# LB_BIT_w6_ARDUINO-v03_4-5_OHW.net
KiCad netlist of a schematic drawn in EAGLE
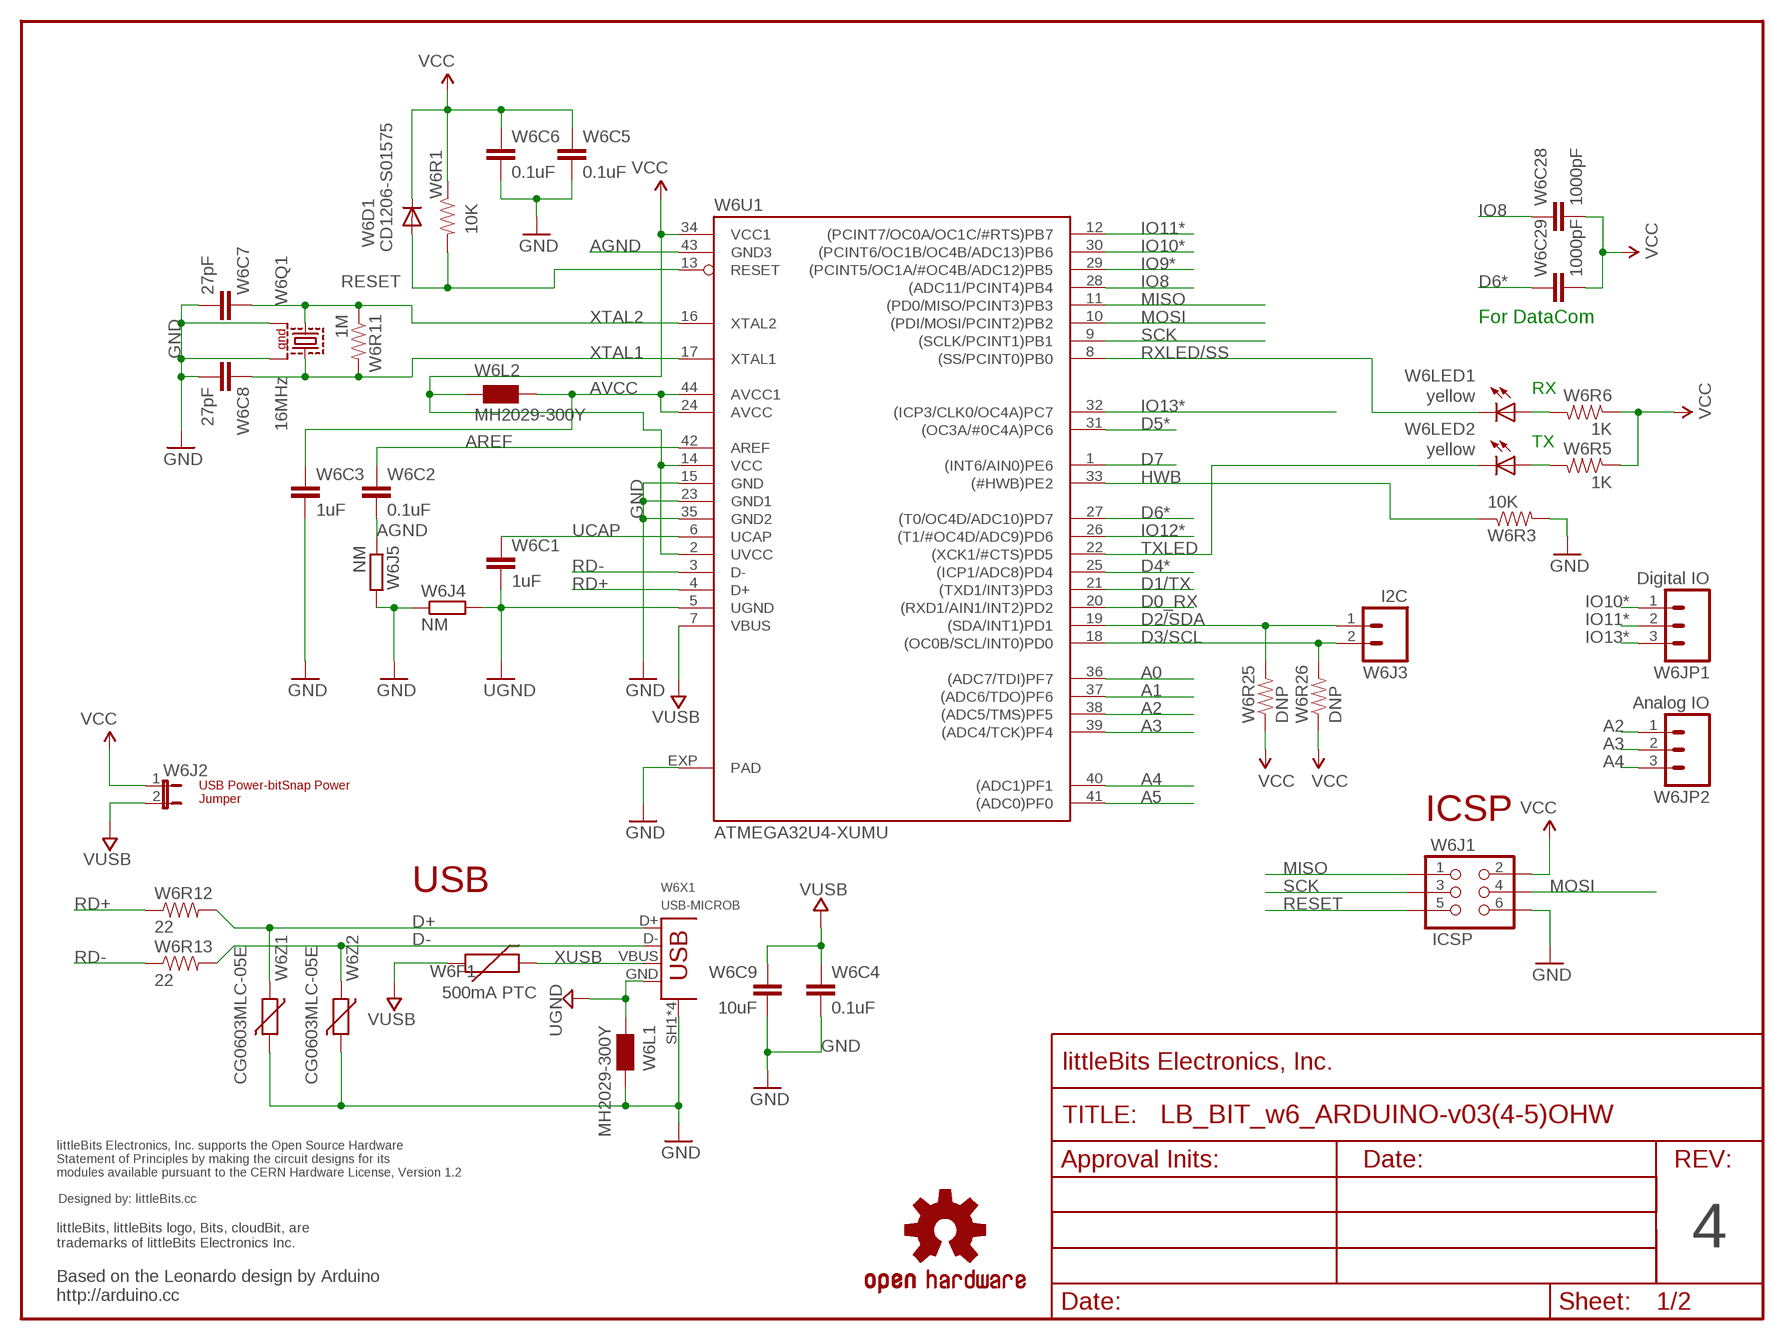
[diagram p0: schematic, sheet 1]
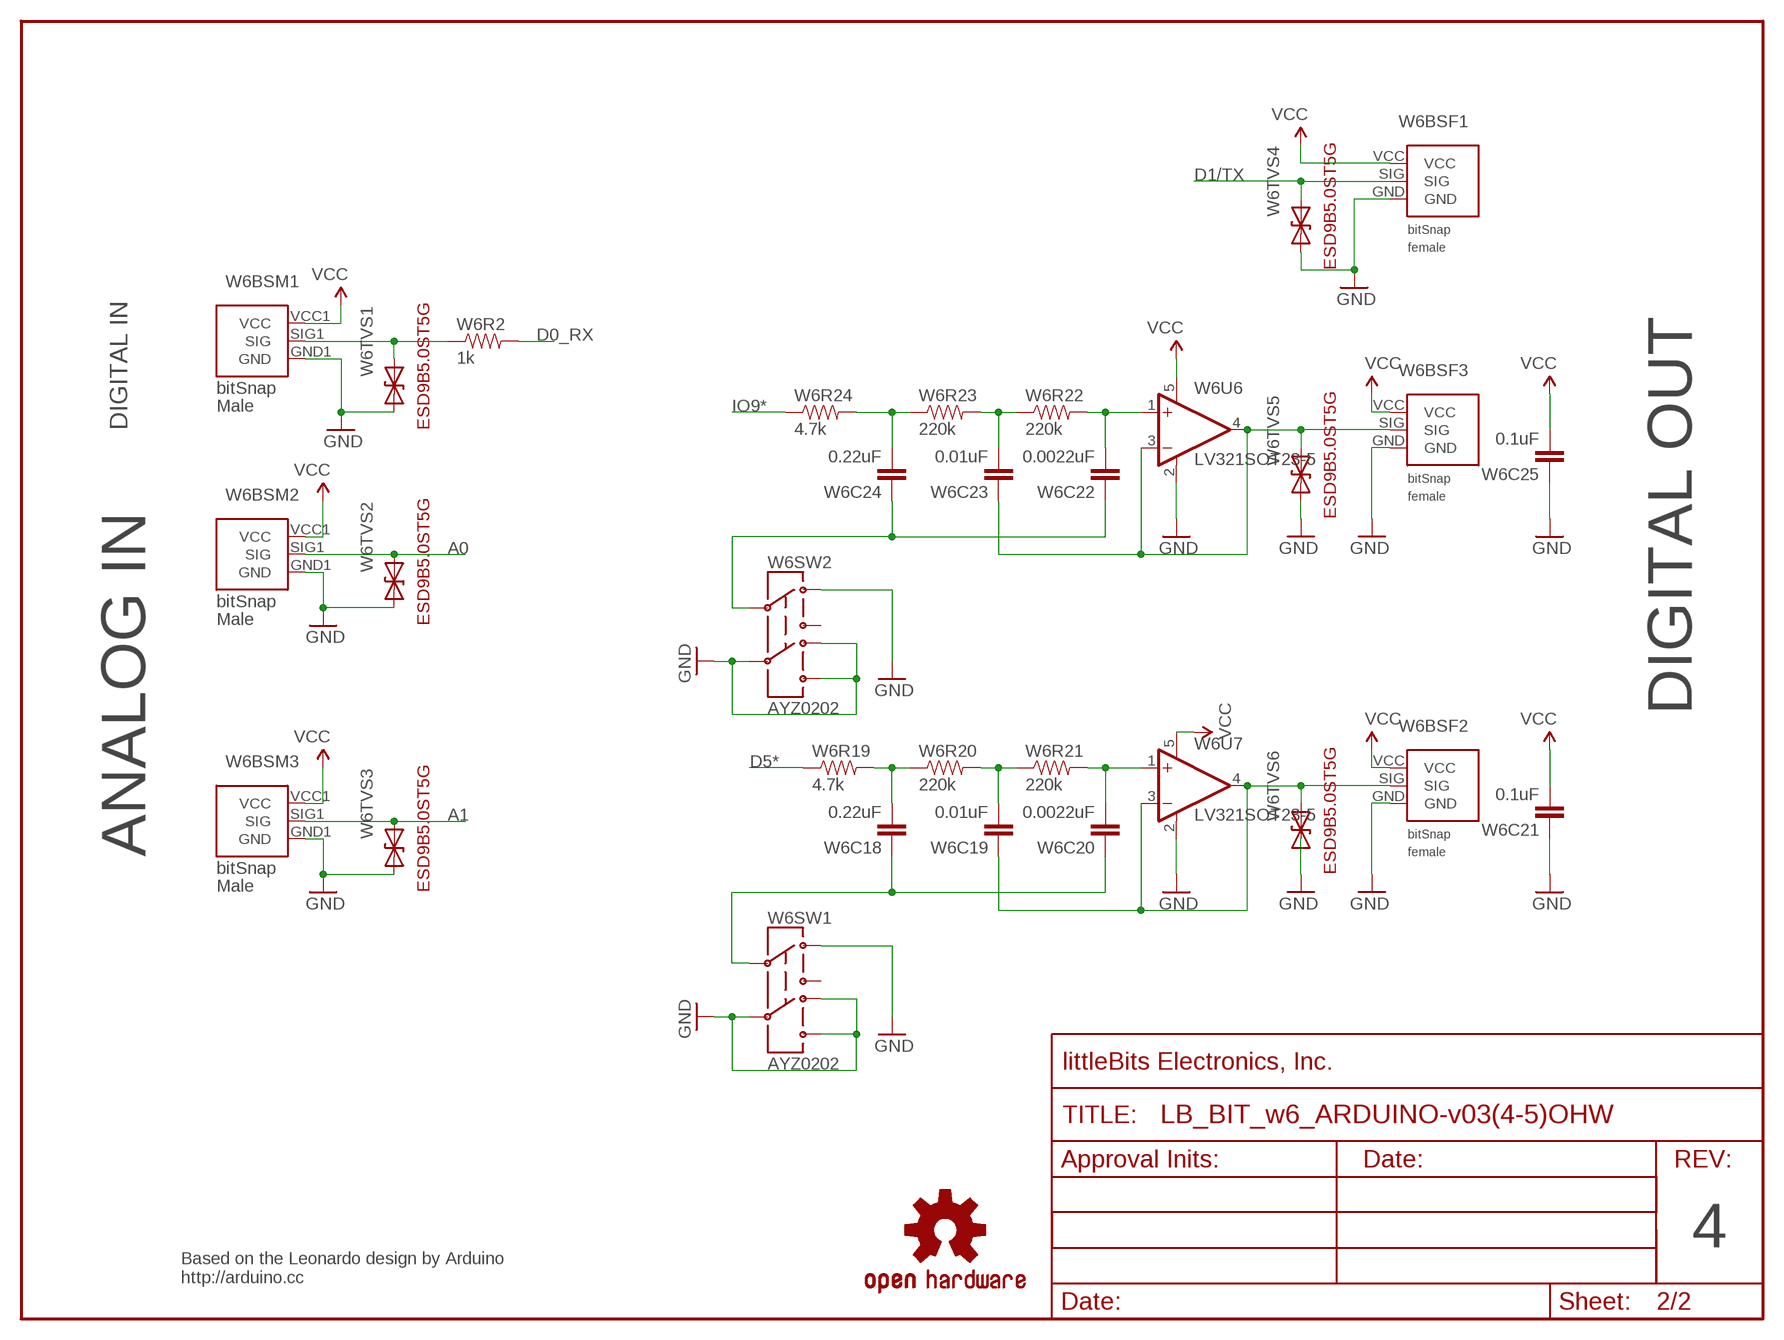
[diagram p1: schematic, sheet 2]

(export (version "E")
  (design (tool "Eeschema 10.0.6"))
  (components
    (comp (ref "FRAME2")
      (value "FRAME-LETTER-OHWOHW")
      (footprint "eagle-import:FABDWG01-OHW")
      (libsource (lib "eagle-import") (part "FRAME-LETTER-OHWOHW"))
    )
    (comp (ref "U$52")
      (value "OSHW-LOGOL")
      (footprint "eagle-import:OSHW-LOGO-L")
      (libsource (lib "eagle-import") (part "OSHW-LOGOL"))
    )
    (comp (ref "U$67")
      (value "OSHWCREDIT")
      (footprint "eagle-import:OSHWCREDIT")
      (libsource (lib "eagle-import") (part "OSHWCREDIT"))
    )
    (comp (ref "W6C1")
      (value "1uF")
      (footprint "eagle-import:CAP-0603")
      (libsource (lib "eagle-import") (part "CAPCAP-0603"))
    )
    (comp (ref "W6C2")
      (value "0.1uF")
      (footprint "eagle-import:CAP-0603")
      (libsource (lib "eagle-import") (part "CAPCAP-0603"))
    )
    (comp (ref "W6C3")
      (value "1uF")
      (footprint "eagle-import:CAP-0603")
      (libsource (lib "eagle-import") (part "CAPCAP-0603"))
    )
    (comp (ref "W6C4")
      (value "0.1uF")
      (footprint "eagle-import:CAP-0603")
      (libsource (lib "eagle-import") (part "CAPCAP-0603"))
    )
    (comp (ref "W6C5")
      (value "0.1uF")
      (footprint "eagle-import:CAP-0603")
      (libsource (lib "eagle-import") (part "CAPCAP-0603"))
    )
    (comp (ref "W6C6")
      (value "0.1uF")
      (footprint "eagle-import:CAP-0603")
      (libsource (lib "eagle-import") (part "CAPCAP-0603"))
    )
    (comp (ref "W6C7")
      (value "27pF")
      (footprint "eagle-import:CAP-0603")
      (libsource (lib "eagle-import") (part "CAPCAP-0603"))
    )
    (comp (ref "W6C8")
      (value "27pF")
      (footprint "eagle-import:CAP-0603")
      (libsource (lib "eagle-import") (part "CAPCAP-0603"))
    )
    (comp (ref "W6C9")
      (value "10uF")
      (footprint "eagle-import:CAP-0805")
      (libsource (lib "eagle-import") (part "CAPCAP-0805"))
    )
    (comp (ref "W6C28")
      (value "1000pF")
      (footprint "eagle-import:CAP-0603")
      (libsource (lib "eagle-import") (part "CAPCAP-0603"))
    )
    (comp (ref "W6C29")
      (value "1000pF")
      (footprint "eagle-import:CAP-0603")
      (libsource (lib "eagle-import") (part "CAPCAP-0603"))
    )
    (comp (ref "W6D1")
      (value "CD1206-S01575")
      (footprint "eagle-import:MINIMELF")
      (libsource (lib "eagle-import") (part "DIODE-MINIMELF"))
    )
    (comp (ref "W6F1")
      (value "500mA PTC")
      (footprint "eagle-import:PTC-1206")
      (libsource (lib "eagle-import") (part "PTC"))
    )
    (comp (ref "W6J1")
      (value "ICSP")
      (footprint "eagle-import:2X03")
      (libsource (lib "eagle-import") (part "HDR-2X3"))
    )
    (comp (ref "W6J2")
      (value "JUMPER-2SMD-NO")
      (footprint "eagle-import:SJ_2S-NO")
      (libsource (lib "eagle-import") (part "JUMPER-2SMD-NO"))
    )
    (comp (ref "W6J3")
      (value "I2C")
      (footprint "eagle-import:SIP2-SM-0.1IN")
      (libsource (lib "eagle-import") (part "HDR-20.1IN_NOS.S."))
    )
    (comp (ref "W6J4")
      (value "NM")
      (footprint "eagle-import:R0402")
      (libsource (lib "eagle-import") (part "R-EU_R0402"))
    )
    (comp (ref "W6J5")
      (value "NM")
      (footprint "eagle-import:R0402")
      (libsource (lib "eagle-import") (part "R-EU_R0402"))
    )
    (comp (ref "W6JP1")
      (value "Digital IO")
      (footprint "eagle-import:1X03")
      (libsource (lib "eagle-import") (part "M03PTH"))
    )
    (comp (ref "W6JP2")
      (value "Analog IO")
      (footprint "eagle-import:1X03")
      (libsource (lib "eagle-import") (part "M03PTH"))
    )
    (comp (ref "W6L1")
      (value "MH2029-300Y")
      (footprint "eagle-import:0805")
      (libsource (lib "eagle-import") (part "WE-CBF_0805"))
    )
    (comp (ref "W6L2")
      (value "MH2029-300Y")
      (footprint "eagle-import:0805")
      (libsource (lib "eagle-import") (part "WE-CBF_0805"))
    )
    (comp (ref "W6LED1")
      (value "yellow")
      (footprint "eagle-import:LED-1206")
      (libsource (lib "eagle-import") (part "LED1206"))
    )
    (comp (ref "W6LED2")
      (value "yellow")
      (footprint "eagle-import:LED-1206")
      (libsource (lib "eagle-import") (part "LED1206"))
    )
    (comp (ref "W6Q1")
      (value "16MHz")
      (footprint "eagle-import:CRYSTAL-SMD-7B-SERIES-5X3.2MM")
      (fields (field (name "MFG") "TXC") (field (name "MPN") "7B SERIES"))
      (libsource (lib "eagle-import") (part "CRYSTAL-SMD-7B-SERIES-TXC"))
    )
    (comp (ref "W6R1")
      (value "10K")
      (footprint "eagle-import:RES-0603")
      (libsource (lib "eagle-import") (part "RESISTOR0603"))
    )
    (comp (ref "W6R3")
      (value "10K")
      (footprint "eagle-import:RES-0603")
      (libsource (lib "eagle-import") (part "RESISTOR0603"))
    )
    (comp (ref "W6R5")
      (value "1K")
      (footprint "eagle-import:RES-0603")
      (libsource (lib "eagle-import") (part "RESISTOR0603"))
    )
    (comp (ref "W6R6")
      (value "1K")
      (footprint "eagle-import:RES-0603")
      (libsource (lib "eagle-import") (part "RESISTOR0603"))
    )
    (comp (ref "W6R11")
      (value "1M")
      (footprint "eagle-import:RES-0603")
      (libsource (lib "eagle-import") (part "RESISTOR0603"))
    )
    (comp (ref "W6R12")
      (value "22")
      (footprint "eagle-import:RES-0603")
      (libsource (lib "eagle-import") (part "RESISTOR0603"))
    )
    (comp (ref "W6R13")
      (value "22")
      (footprint "eagle-import:RES-0603")
      (libsource (lib "eagle-import") (part "RESISTOR0603"))
    )
    (comp (ref "W6R25")
      (value "DNP")
      (footprint "eagle-import:RES-0603")
      (libsource (lib "eagle-import") (part "RESISTOR0603"))
    )
    (comp (ref "W6R26")
      (value "DNP")
      (footprint "eagle-import:RES-0603")
      (libsource (lib "eagle-import") (part "RESISTOR0603"))
    )
    (comp (ref "W6U1")
      (value "ATMEGA32U4-XUMU")
      (footprint "eagle-import:QFN44ML7X7")
      (libsource (lib "eagle-import") (part "ATMEGA32U4-XUMU"))
    )
    (comp (ref "W6X1")
      (value "USB-MICROB")
      (footprint "eagle-import:USB-MICROB-AUK-DRILLS")
      (fields (field (name "MFG") "AUK") (field (name "MPN") "MCSB5ABSW-4-GXX-R1K-H"))
      (libsource (lib "eagle-import") (part "USB-MICROB-DRILLS"))
    )
    (comp (ref "W6Z1")
      (value "CG0603MLC-05E")
      (footprint "eagle-import:CT_CN0603")
      (libsource (lib "eagle-import") (part "VARISTORCN0603"))
    )
    (comp (ref "W6Z2")
      (value "CG0603MLC-05E")
      (footprint "eagle-import:CT_CN0603")
      (libsource (lib "eagle-import") (part "VARISTORCN0603"))
    )
    (comp (ref "U$54")
      (value "FRAME-LETTER-OHWOHW")
      (footprint "eagle-import:FABDWG01-OHW")
      (libsource (lib "eagle-import") (part "FRAME-LETTER-OHWOHW"))
    )
    (comp (ref "U$70")
      (value "OSHW-LOGOL")
      (footprint "eagle-import:OSHW-LOGO-L")
      (libsource (lib "eagle-import") (part "OSHW-LOGOL"))
    )
    (comp (ref "W6BSF1")
      (value "BITSNAP_V03_FEMALE")
      (footprint "eagle-import:BITSNAP_V03_FEMALE")
      (libsource (lib "eagle-import") (part "BITSNAP_V03_FEMALE"))
    )
    (comp (ref "W6BSF2")
      (value "BITSNAP_V03_FEMALE")
      (footprint "eagle-import:BITSNAP_V03_FEMALE")
      (libsource (lib "eagle-import") (part "BITSNAP_V03_FEMALE"))
    )
    (comp (ref "W6BSF3")
      (value "BITSNAP_V03_FEMALE")
      (footprint "eagle-import:BITSNAP_V03_FEMALE")
      (libsource (lib "eagle-import") (part "BITSNAP_V03_FEMALE"))
    )
    (comp (ref "W6BSM1")
      (value "BITSNAP_V03_MALE")
      (footprint "eagle-import:BITSNAP_V03_MALE")
      (libsource (lib "eagle-import") (part "BITSNAP_V03_MALE"))
    )
    (comp (ref "W6BSM2")
      (value "BITSNAP_V03_MALE")
      (footprint "eagle-import:BITSNAP_V03_MALE")
      (libsource (lib "eagle-import") (part "BITSNAP_V03_MALE"))
    )
    (comp (ref "W6BSM3")
      (value "BITSNAP_V03_MALE")
      (footprint "eagle-import:BITSNAP_V03_MALE")
      (libsource (lib "eagle-import") (part "BITSNAP_V03_MALE"))
    )
    (comp (ref "W6C18")
      (value "0.22uF")
      (footprint "eagle-import:CAP-0603")
      (libsource (lib "eagle-import") (part "CAPCAP-0603"))
    )
    (comp (ref "W6C19")
      (value "0.01uF")
      (footprint "eagle-import:CAP-0603")
      (libsource (lib "eagle-import") (part "CAPCAP-0603"))
    )
    (comp (ref "W6C20")
      (value "0.0022uF")
      (footprint "eagle-import:CAP-0603")
      (libsource (lib "eagle-import") (part "CAPCAP-0603"))
    )
    (comp (ref "W6C21")
      (value "0.1uF")
      (footprint "eagle-import:CAP-0603")
      (libsource (lib "eagle-import") (part "CAPCAP-0603"))
    )
    (comp (ref "W6C22")
      (value "0.0022uF")
      (footprint "eagle-import:CAP-0603")
      (libsource (lib "eagle-import") (part "CAPCAP-0603"))
    )
    (comp (ref "W6C23")
      (value "0.01uF")
      (footprint "eagle-import:CAP-0603")
      (libsource (lib "eagle-import") (part "CAPCAP-0603"))
    )
    (comp (ref "W6C24")
      (value "0.22uF")
      (footprint "eagle-import:CAP-0603")
      (libsource (lib "eagle-import") (part "CAPCAP-0603"))
    )
    (comp (ref "W6C25")
      (value "0.1uF")
      (footprint "eagle-import:CAP-0603")
      (libsource (lib "eagle-import") (part "CAPCAP-0603"))
    )
    (comp (ref "W6R2")
      (value "1k")
      (footprint "eagle-import:RES-0603")
      (libsource (lib "eagle-import") (part "RESISTOR0603"))
    )
    (comp (ref "W6R19")
      (value "4.7k")
      (footprint "eagle-import:RES-0603")
      (libsource (lib "eagle-import") (part "RESISTOR0603"))
    )
    (comp (ref "W6R20")
      (value "220k")
      (footprint "eagle-import:RES-0603")
      (libsource (lib "eagle-import") (part "RESISTOR0603"))
    )
    (comp (ref "W6R21")
      (value "220k")
      (footprint "eagle-import:RES-0603")
      (libsource (lib "eagle-import") (part "RESISTOR0603"))
    )
    (comp (ref "W6R22")
      (value "220k")
      (footprint "eagle-import:RES-0603")
      (libsource (lib "eagle-import") (part "RESISTOR0603"))
    )
    (comp (ref "W6R23")
      (value "220k")
      (footprint "eagle-import:RES-0603")
      (libsource (lib "eagle-import") (part "RESISTOR0603"))
    )
    (comp (ref "W6R24")
      (value "4.7k")
      (footprint "eagle-import:RES-0603")
      (libsource (lib "eagle-import") (part "RESISTOR0603"))
    )
    (comp (ref "W6SW1")
      (value "AYZ0202")
      (footprint "eagle-import:AYZ0202")
      (libsource (lib "eagle-import") (part "AYZ0202"))
    )
    (comp (ref "W6SW2")
      (value "AYZ0202")
      (footprint "eagle-import:AYZ0202")
      (libsource (lib "eagle-import") (part "AYZ0202"))
    )
    (comp (ref "W6TVS1")
      (value "DIODE-TVSSOD-923")
      (footprint "eagle-import:SOD-923")
      (fields (field (name "MPN") "ESD9B5.0ST5G"))
      (libsource (lib "eagle-import") (part "DIODE-TVSSOD-923"))
    )
    (comp (ref "W6TVS2")
      (value "DIODE-TVSSOD-923")
      (footprint "eagle-import:SOD-923")
      (fields (field (name "MPN") "ESD9B5.0ST5G"))
      (libsource (lib "eagle-import") (part "DIODE-TVSSOD-923"))
    )
    (comp (ref "W6TVS3")
      (value "DIODE-TVSSOD-923")
      (footprint "eagle-import:SOD-923")
      (fields (field (name "MPN") "ESD9B5.0ST5G"))
      (libsource (lib "eagle-import") (part "DIODE-TVSSOD-923"))
    )
    (comp (ref "W6TVS4")
      (value "DIODE-TVSSOD-923")
      (footprint "eagle-import:SOD-923")
      (fields (field (name "MPN") "ESD9B5.0ST5G"))
      (libsource (lib "eagle-import") (part "DIODE-TVSSOD-923"))
    )
    (comp (ref "W6TVS5")
      (value "DIODE-TVSSOD-923")
      (footprint "eagle-import:SOD-923")
      (fields (field (name "MPN") "ESD9B5.0ST5G"))
      (libsource (lib "eagle-import") (part "DIODE-TVSSOD-923"))
    )
    (comp (ref "W6TVS6")
      (value "DIODE-TVSSOD-923")
      (footprint "eagle-import:SOD-923")
      (fields (field (name "MPN") "ESD9B5.0ST5G"))
      (libsource (lib "eagle-import") (part "DIODE-TVSSOD-923"))
    )
    (comp (ref "W6U6")
      (value "LV321SOT23-5")
      (footprint "eagle-import:SOT23-5")
      (libsource (lib "eagle-import") (part "LV321SOT23-5"))
    )
    (comp (ref "W6U7")
      (value "LV321SOT23-5")
      (footprint "eagle-import:SOT23-5")
      (libsource (lib "eagle-import") (part "LV321SOT23-5"))
    )
  )
  (nets
    (net (code "1") (name "A0") (class "Default")
      (node (ref "W6BSM2") (pin "SIG1") (pinfunction "SIG_SIG1") (pintype "bidirectional"))
      (node (ref "W6TVS2") (pin "2") (pinfunction "C_2") (pintype "passive"))
      (node (ref "W6U1") (pin "36") (pinfunction "(ADC7/TDI)PF7_36") (pintype "bidirectional"))
    )
    (net (code "2") (name "A1") (class "Default")
      (node (ref "W6BSM3") (pin "SIG1") (pinfunction "SIG_SIG1") (pintype "bidirectional"))
      (node (ref "W6TVS3") (pin "2") (pinfunction "C_2") (pintype "passive"))
      (node (ref "W6U1") (pin "37") (pinfunction "(ADC6/TDO)PF6_37") (pintype "bidirectional"))
    )
    (net (code "3") (name "A2") (class "Default")
      (node (ref "W6JP2") (pin "1") (pinfunction "1_1") (pintype "passive"))
      (node (ref "W6U1") (pin "38") (pinfunction "(ADC5/TMS)PF5_38") (pintype "bidirectional"))
    )
    (net (code "4") (name "A3") (class "Default")
      (node (ref "W6JP2") (pin "2") (pinfunction "2_2") (pintype "passive"))
      (node (ref "W6U1") (pin "39") (pinfunction "(ADC4/TCK)PF4_39") (pintype "bidirectional"))
    )
    (net (code "5") (name "A4") (class "Default")
      (node (ref "W6JP2") (pin "3") (pinfunction "3_3") (pintype "passive"))
      (node (ref "W6U1") (pin "40") (pinfunction "(ADC1)PF1_40") (pintype "bidirectional"))
    )
    (net (code "6") (name "A5") (class "Default")
      (node (ref "W6U1") (pin "41") (pinfunction "(ADC0)PF0_41") (pintype "bidirectional"))
    )
    (net (code "7") (name "AGND") (class "Default")
      (node (ref "W6C2") (pin "2") (pinfunction "2_2") (pintype "passive"))
      (node (ref "W6J5") (pin "1") (pinfunction "1_1") (pintype "passive"))
      (node (ref "W6U1") (pin "43") (pinfunction "GND3_43") (pintype "power_in"))
    )
    (net (code "8") (name "AREF") (class "Default")
      (node (ref "W6C2") (pin "1") (pinfunction "1_1") (pintype "passive"))
      (node (ref "W6U1") (pin "42") (pinfunction "AREF_42") (pintype "power_in"))
    )
    (net (code "9") (name "AVCC") (class "Default")
      (node (ref "W6C3") (pin "1") (pinfunction "1_1") (pintype "passive"))
      (node (ref "W6L2") (pin "2") (pinfunction "2_2") (pintype "passive"))
      (node (ref "W6U1") (pin "24") (pinfunction "AVCC_24") (pintype "power_in"))
      (node (ref "W6U1") (pin "44") (pinfunction "AVCC1_44") (pintype "power_in"))
    )
    (net (code "10") (name "D+") (class "Default")
      (node (ref "W6R12") (pin "2") (pinfunction "2_2") (pintype "passive"))
      (node (ref "W6X1") (pin "D+") (pinfunction "D+_D+") (pintype "bidirectional"))
      (node (ref "W6Z1") (pin "1") (pinfunction "1_1") (pintype "passive"))
    )
    (net (code "11") (name "D-") (class "Default")
      (node (ref "W6R13") (pin "2") (pinfunction "2_2") (pintype "passive"))
      (node (ref "W6X1") (pin "D-") (pinfunction "D-_D-") (pintype "bidirectional"))
      (node (ref "W6Z2") (pin "1") (pinfunction "1_1") (pintype "passive"))
    )
    (net (code "12") (name "D0_RX") (class "Default")
      (node (ref "W6R2") (pin "2") (pinfunction "2_2") (pintype "passive"))
      (node (ref "W6U1") (pin "20") (pinfunction "(RXD1/AIN1/INT2)PD2_20") (pintype "bidirectional"))
    )
    (net (code "13") (name "D1{slash}TX") (class "Default")
      (node (ref "W6BSF1") (pin "SIG") (pinfunction "SIG_SIG") (pintype "bidirectional"))
      (node (ref "W6TVS4") (pin "2") (pinfunction "C_2") (pintype "passive"))
      (node (ref "W6U1") (pin "21") (pinfunction "(TXD1/INT3)PD3_21") (pintype "bidirectional"))
    )
    (net (code "14") (name "D2{slash}SDA") (class "Default")
      (node (ref "W6J3") (pin "1") (pinfunction "1_1") (pintype "passive"))
      (node (ref "W6R25") (pin "2") (pinfunction "2_2") (pintype "passive"))
      (node (ref "W6U1") (pin "19") (pinfunction "(SDA/INT1)PD1_19") (pintype "bidirectional"))
    )
    (net (code "15") (name "D3{slash}SCL") (class "Default")
      (node (ref "W6J3") (pin "2") (pinfunction "2_2") (pintype "passive"))
      (node (ref "W6R26") (pin "2") (pinfunction "2_2") (pintype "passive"))
      (node (ref "W6U1") (pin "18") (pinfunction "(OC0B/SCL/INT0)PD0_18") (pintype "bidirectional"))
    )
    (net (code "16") (name "D4*") (class "Default")
      (node (ref "W6U1") (pin "25") (pinfunction "(ICP1/ADC8)PD4_25") (pintype "bidirectional"))
    )
    (net (code "17") (name "D5*") (class "Default")
      (node (ref "W6R19") (pin "1") (pinfunction "1_1") (pintype "passive"))
      (node (ref "W6U1") (pin "31") (pinfunction "(OC3A/#0C4A)PC6_31") (pintype "bidirectional"))
    )
    (net (code "18") (name "D6*") (class "Default")
      (node (ref "W6C29") (pin "1") (pinfunction "1_1") (pintype "passive"))
      (node (ref "W6U1") (pin "27") (pinfunction "(T0/OC4D/ADC10)PD7_27") (pintype "bidirectional"))
    )
    (net (code "19") (name "D7") (class "Default")
      (node (ref "W6U1") (pin "1") (pinfunction "(INT6/AIN0)PE6_1") (pintype "bidirectional"))
    )
    (net (code "20") (name "GND") (class "Default")
      (node (ref "W6BSF1") (pin "GND") (pinfunction "GND_GND") (pintype "bidirectional"))
      (node (ref "W6BSF2") (pin "GND") (pinfunction "GND_GND") (pintype "bidirectional"))
      (node (ref "W6BSF3") (pin "GND") (pinfunction "GND_GND") (pintype "bidirectional"))
      (node (ref "W6BSM1") (pin "GND1") (pinfunction "GND_GND1") (pintype "bidirectional"))
      (node (ref "W6BSM2") (pin "GND1") (pinfunction "GND_GND1") (pintype "bidirectional"))
      (node (ref "W6BSM3") (pin "GND1") (pinfunction "GND_GND1") (pintype "bidirectional"))
      (node (ref "W6C21") (pin "1") (pinfunction "1_1") (pintype "passive"))
      (node (ref "W6C25") (pin "1") (pinfunction "1_1") (pintype "passive"))
      (node (ref "W6C3") (pin "2") (pinfunction "2_2") (pintype "passive"))
      (node (ref "W6C4") (pin "2") (pinfunction "2_2") (pintype "passive"))
      (node (ref "W6C5") (pin "2") (pinfunction "2_2") (pintype "passive"))
      (node (ref "W6C6") (pin "2") (pinfunction "2_2") (pintype "passive"))
      (node (ref "W6C7") (pin "2") (pinfunction "2_2") (pintype "passive"))
      (node (ref "W6C8") (pin "2") (pinfunction "2_2") (pintype "passive"))
      (node (ref "W6C9") (pin "2") (pinfunction "2_2") (pintype "passive"))
      (node (ref "W6J1") (pin "6") (pinfunction "6_6") (pintype "passive"))
      (node (ref "W6J4") (pin "1") (pinfunction "1_1") (pintype "passive"))
      (node (ref "W6J5") (pin "2") (pinfunction "2_2") (pintype "passive"))
      (node (ref "W6L1") (pin "2") (pinfunction "2_2") (pintype "passive"))
      (node (ref "W6Q1") (pin "P$2") (pinfunction "2_P$2") (pintype "passive"))
      (node (ref "W6Q1") (pin "P$4") (pinfunction "4_P$4") (pintype "passive"))
      (node (ref "W6R3") (pin "2") (pinfunction "2_2") (pintype "passive"))
      (node (ref "W6SW1") (pin "1") (pinfunction "1_1") (pintype "bidirectional"))
      (node (ref "W6SW1") (pin "4") (pinfunction "4_4") (pintype "bidirectional"))
      (node (ref "W6SW1") (pin "5") (pinfunction "5_5") (pintype "bidirectional"))
      (node (ref "W6SW1") (pin "6") (pinfunction "6_6") (pintype "bidirectional"))
      (node (ref "W6SW2") (pin "1") (pinfunction "1_1") (pintype "bidirectional"))
      (node (ref "W6SW2") (pin "4") (pinfunction "4_4") (pintype "bidirectional"))
      (node (ref "W6SW2") (pin "5") (pinfunction "5_5") (pintype "bidirectional"))
      (node (ref "W6SW2") (pin "6") (pinfunction "6_6") (pintype "bidirectional"))
      (node (ref "W6TVS1") (pin "1") (pinfunction "A_1") (pintype "passive"))
      (node (ref "W6TVS2") (pin "1") (pinfunction "A_1") (pintype "passive"))
      (node (ref "W6TVS3") (pin "1") (pinfunction "A_1") (pintype "passive"))
      (node (ref "W6TVS4") (pin "1") (pinfunction "A_1") (pintype "passive"))
      (node (ref "W6TVS5") (pin "1") (pinfunction "A_1") (pintype "passive"))
      (node (ref "W6TVS6") (pin "1") (pinfunction "A_1") (pintype "passive"))
      (node (ref "W6U1") (pin "15") (pinfunction "GND_15") (pintype "power_in"))
      (node (ref "W6U1") (pin "23") (pinfunction "GND1_23") (pintype "power_in"))
      (node (ref "W6U1") (pin "35") (pinfunction "GND2_35") (pintype "power_in"))
      (node (ref "W6U1") (pin "EXP") (pinfunction "PAD_EXP") (pintype "power_in"))
      (node (ref "W6U6") (pin "2") (pinfunction "V-_2") (pintype "power_in"))
      (node (ref "W6U7") (pin "2") (pinfunction "V-_2") (pintype "power_in"))
      (node (ref "W6X1") (pin "SH1") (pinfunction "SH_SH1") (pintype "bidirectional"))
      (node (ref "W6X1") (pin "SH2") (pinfunction "SH_SH2") (pintype "bidirectional"))
      (node (ref "W6X1") (pin "SH3") (pinfunction "SH_SH3") (pintype "bidirectional"))
      (node (ref "W6X1") (pin "SH4") (pinfunction "SH_SH4") (pintype "bidirectional"))
      (node (ref "W6Z1") (pin "2") (pinfunction "2_2") (pintype "passive"))
      (node (ref "W6Z2") (pin "2") (pinfunction "2_2") (pintype "passive"))
    )
    (net (code "21") (name "HWB") (class "Default")
      (node (ref "W6R3") (pin "1") (pinfunction "1_1") (pintype "passive"))
      (node (ref "W6U1") (pin "33") (pinfunction "(#HWB)PE2_33") (pintype "bidirectional"))
    )
    (net (code "22") (name "IO8") (class "Default")
      (node (ref "W6C28") (pin "1") (pinfunction "1_1") (pintype "passive"))
      (node (ref "W6U1") (pin "28") (pinfunction "(ADC11/PCINT4)PB4_28") (pintype "bidirectional"))
    )
    (net (code "23") (name "IO9*") (class "Default")
      (node (ref "W6R24") (pin "1") (pinfunction "1_1") (pintype "passive"))
      (node (ref "W6U1") (pin "29") (pinfunction "(PCINT5/OC1A/#OC4B/ADC12)PB5_29") (pintype "bidirectional"))
    )
    (net (code "24") (name "IO10*") (class "Default")
      (node (ref "W6JP1") (pin "1") (pinfunction "1_1") (pintype "passive"))
      (node (ref "W6U1") (pin "30") (pinfunction "(PCINT6/OC1B/OC4B/ADC13)PB6_30") (pintype "bidirectional"))
    )
    (net (code "25") (name "IO11*") (class "Default")
      (node (ref "W6JP1") (pin "2") (pinfunction "2_2") (pintype "passive"))
      (node (ref "W6U1") (pin "12") (pinfunction "(PCINT7/OC0A/OC1C/#RTS)PB7_12") (pintype "bidirectional"))
    )
    (net (code "26") (name "IO12*") (class "Default")
      (node (ref "W6U1") (pin "26") (pinfunction "(T1/#OC4D/ADC9)PD6_26") (pintype "bidirectional"))
    )
    (net (code "27") (name "IO13*") (class "Default")
      (node (ref "W6JP1") (pin "3") (pinfunction "3_3") (pintype "passive"))
      (node (ref "W6U1") (pin "32") (pinfunction "(ICP3/CLK0/OC4A)PC7_32") (pintype "bidirectional"))
    )
    (net (code "28") (name "MISO") (class "Default")
      (node (ref "W6J1") (pin "1") (pinfunction "1_1") (pintype "passive"))
      (node (ref "W6U1") (pin "11") (pinfunction "(PD0/MISO/PCINT3)PB3_11") (pintype "bidirectional"))
    )
    (net (code "29") (name "MOSI") (class "Default")
      (node (ref "W6J1") (pin "4") (pinfunction "4_4") (pintype "passive"))
      (node (ref "W6U1") (pin "10") (pinfunction "(PDI/MOSI/PCINT2)PB2_10") (pintype "bidirectional"))
    )
    (net (code "30") (name "Net-(W6BSM1-SIG)") (class "Default")
      (node (ref "W6BSM1") (pin "SIG1") (pinfunction "SIG_SIG1") (pintype "bidirectional"))
      (node (ref "W6R2") (pin "1") (pinfunction "1_1") (pintype "passive"))
      (node (ref "W6TVS1") (pin "2") (pinfunction "C_2") (pintype "passive"))
    )
    (net (code "31") (name "Net-(W6C18-Pad1)") (class "Default")
      (node (ref "W6C18") (pin "1") (pinfunction "1_1") (pintype "passive"))
      (node (ref "W6C20") (pin "1") (pinfunction "1_1") (pintype "passive"))
      (node (ref "W6SW1") (pin "2") (pinfunction "2_2") (pintype "bidirectional"))
    )
    (net (code "32") (name "Net-(W6C18-Pad2)") (class "Default")
      (node (ref "W6C18") (pin "2") (pinfunction "2_2") (pintype "passive"))
      (node (ref "W6R19") (pin "2") (pinfunction "2_2") (pintype "passive"))
      (node (ref "W6R20") (pin "1") (pinfunction "1_1") (pintype "passive"))
    )
    (net (code "33") (name "Net-(W6C19-Pad2)") (class "Default")
      (node (ref "W6C19") (pin "2") (pinfunction "2_2") (pintype "passive"))
      (node (ref "W6R20") (pin "2") (pinfunction "2_2") (pintype "passive"))
      (node (ref "W6R21") (pin "1") (pinfunction "1_1") (pintype "passive"))
    )
    (net (code "34") (name "Net-(W6C22-Pad1)") (class "Default")
      (node (ref "W6C22") (pin "1") (pinfunction "1_1") (pintype "passive"))
      (node (ref "W6C24") (pin "1") (pinfunction "1_1") (pintype "passive"))
      (node (ref "W6SW2") (pin "2") (pinfunction "2_2") (pintype "bidirectional"))
    )
    (net (code "35") (name "Net-(W6C23-Pad2)") (class "Default")
      (node (ref "W6C23") (pin "2") (pinfunction "2_2") (pintype "passive"))
      (node (ref "W6R22") (pin "1") (pinfunction "1_1") (pintype "passive"))
      (node (ref "W6R23") (pin "2") (pinfunction "2_2") (pintype "passive"))
    )
    (net (code "36") (name "Net-(W6C24-Pad2)") (class "Default")
      (node (ref "W6C24") (pin "2") (pinfunction "2_2") (pintype "passive"))
      (node (ref "W6R23") (pin "1") (pinfunction "1_1") (pintype "passive"))
      (node (ref "W6R24") (pin "2") (pinfunction "2_2") (pintype "passive"))
    )
    (net (code "37") (name "Net-(W6LED1-PadA)") (class "Default")
      (node (ref "W6LED1") (pin "A") (pinfunction "A_A") (pintype "passive"))
      (node (ref "W6R6") (pin "2") (pinfunction "2_2") (pintype "passive"))
    )
    (net (code "38") (name "Net-(W6LED2-PadA)") (class "Default")
      (node (ref "W6LED2") (pin "A") (pinfunction "A_A") (pintype "passive"))
      (node (ref "W6R5") (pin "2") (pinfunction "2_2") (pintype "passive"))
    )
    (net (code "39") (name "Net-(W6TVS5-C)") (class "Default")
      (node (ref "W6BSF3") (pin "SIG") (pinfunction "SIG_SIG") (pintype "bidirectional"))
      (node (ref "W6C23") (pin "1") (pinfunction "1_1") (pintype "passive"))
      (node (ref "W6TVS5") (pin "2") (pinfunction "C_2") (pintype "passive"))
      (node (ref "W6U6") (pin "3") (pinfunction "-IN_3") (pintype "input"))
      (node (ref "W6U6") (pin "4") (pinfunction "OUT_4") (pintype "output"))
    )
    (net (code "40") (name "Net-(W6TVS6-C)") (class "Default")
      (node (ref "W6BSF2") (pin "SIG") (pinfunction "SIG_SIG") (pintype "bidirectional"))
      (node (ref "W6C19") (pin "1") (pinfunction "1_1") (pintype "passive"))
      (node (ref "W6TVS6") (pin "2") (pinfunction "C_2") (pintype "passive"))
      (node (ref "W6U7") (pin "3") (pinfunction "-IN_3") (pintype "input"))
      (node (ref "W6U7") (pin "4") (pinfunction "OUT_4") (pintype "output"))
    )
    (net (code "41") (name "Net-(W6U6-+IN)") (class "Default")
      (node (ref "W6C22") (pin "2") (pinfunction "2_2") (pintype "passive"))
      (node (ref "W6R22") (pin "2") (pinfunction "2_2") (pintype "passive"))
      (node (ref "W6U6") (pin "1") (pinfunction "+IN_1") (pintype "input"))
    )
    (net (code "42") (name "Net-(W6U7-+IN)") (class "Default")
      (node (ref "W6C20") (pin "2") (pinfunction "2_2") (pintype "passive"))
      (node (ref "W6R21") (pin "2") (pinfunction "2_2") (pintype "passive"))
      (node (ref "W6U7") (pin "1") (pinfunction "+IN_1") (pintype "input"))
    )
    (net (code "43") (name "RD+") (class "Default")
      (node (ref "W6R12") (pin "1") (pinfunction "1_1") (pintype "passive"))
      (node (ref "W6U1") (pin "4") (pinfunction "D+_4") (pintype "bidirectional"))
    )
    (net (code "44") (name "RD-") (class "Default")
      (node (ref "W6R13") (pin "1") (pinfunction "1_1") (pintype "passive"))
      (node (ref "W6U1") (pin "3") (pinfunction "D-_3") (pintype "bidirectional"))
    )
    (net (code "45") (name "RESET") (class "Default")
      (node (ref "W6D1") (pin "A") (pinfunction "A_A") (pintype "passive"))
      (node (ref "W6J1") (pin "5") (pinfunction "5_5") (pintype "passive"))
      (node (ref "W6R1") (pin "2") (pinfunction "2_2") (pintype "passive"))
      (node (ref "W6U1") (pin "13") (pinfunction "RESET_13") (pintype "input"))
    )
    (net (code "46") (name "RXLED{slash}SS") (class "Default")
      (node (ref "W6LED1") (pin "C") (pinfunction "C_C") (pintype "passive"))
      (node (ref "W6U1") (pin "8") (pinfunction "(SS/PCINT0)PB0_8") (pintype "bidirectional"))
    )
    (net (code "47") (name "SCK") (class "Default")
      (node (ref "W6J1") (pin "3") (pinfunction "3_3") (pintype "passive"))
      (node (ref "W6U1") (pin "9") (pinfunction "(SCLK/PCINT1)PB1_9") (pintype "bidirectional"))
    )
    (net (code "48") (name "TXLED") (class "Default")
      (node (ref "W6LED2") (pin "C") (pinfunction "C_C") (pintype "passive"))
      (node (ref "W6U1") (pin "22") (pinfunction "(XCK1/#CTS)PD5_22") (pintype "bidirectional"))
    )
    (net (code "49") (name "UCAP") (class "Default")
      (node (ref "W6C1") (pin "1") (pinfunction "1_1") (pintype "passive"))
      (node (ref "W6U1") (pin "6") (pinfunction "UCAP_6") (pintype "passive"))
    )
    (net (code "50") (name "UGND") (class "Default")
      (node (ref "W6C1") (pin "2") (pinfunction "2_2") (pintype "passive"))
      (node (ref "W6J4") (pin "2") (pinfunction "2_2") (pintype "passive"))
      (node (ref "W6L1") (pin "1") (pinfunction "1_1") (pintype "passive"))
      (node (ref "W6U1") (pin "5") (pinfunction "UGND_5") (pintype "power_in"))
      (node (ref "W6X1") (pin "GND") (pinfunction "GND_GND") (pintype "bidirectional"))
    )
    (net (code "51") (name "VCC") (class "Default")
      (node (ref "W6BSF1") (pin "VCC") (pinfunction "VCC_VCC") (pintype "bidirectional"))
      (node (ref "W6BSF2") (pin "VCC") (pinfunction "VCC_VCC") (pintype "bidirectional"))
      (node (ref "W6BSF3") (pin "VCC") (pinfunction "VCC_VCC") (pintype "bidirectional"))
      (node (ref "W6BSM1") (pin "VCC1") (pinfunction "VCC_VCC1") (pintype "bidirectional"))
      (node (ref "W6BSM2") (pin "VCC1") (pinfunction "VCC_VCC1") (pintype "bidirectional"))
      (node (ref "W6BSM3") (pin "VCC1") (pinfunction "VCC_VCC1") (pintype "bidirectional"))
      (node (ref "W6C21") (pin "2") (pinfunction "2_2") (pintype "passive"))
      (node (ref "W6C25") (pin "2") (pinfunction "2_2") (pintype "passive"))
      (node (ref "W6C28") (pin "2") (pinfunction "2_2") (pintype "passive"))
      (node (ref "W6C29") (pin "2") (pinfunction "2_2") (pintype "passive"))
      (node (ref "W6C5") (pin "1") (pinfunction "1_1") (pintype "passive"))
      (node (ref "W6C6") (pin "1") (pinfunction "1_1") (pintype "passive"))
      (node (ref "W6D1") (pin "C") (pinfunction "C_C") (pintype "passive"))
      (node (ref "W6J1") (pin "2") (pinfunction "2_2") (pintype "passive"))
      (node (ref "W6J2") (pin "1") (pinfunction "1_1") (pintype "passive"))
      (node (ref "W6L2") (pin "1") (pinfunction "1_1") (pintype "passive"))
      (node (ref "W6R1") (pin "1") (pinfunction "1_1") (pintype "passive"))
      (node (ref "W6R25") (pin "1") (pinfunction "1_1") (pintype "passive"))
      (node (ref "W6R26") (pin "1") (pinfunction "1_1") (pintype "passive"))
      (node (ref "W6R5") (pin "1") (pinfunction "1_1") (pintype "passive"))
      (node (ref "W6R6") (pin "1") (pinfunction "1_1") (pintype "passive"))
      (node (ref "W6U1") (pin "14") (pinfunction "VCC_14") (pintype "power_in"))
      (node (ref "W6U1") (pin "2") (pinfunction "UVCC_2") (pintype "power_in"))
      (node (ref "W6U1") (pin "34") (pinfunction "VCC1_34") (pintype "power_in"))
      (node (ref "W6U6") (pin "5") (pinfunction "V+_5") (pintype "power_in"))
      (node (ref "W6U7") (pin "5") (pinfunction "V+_5") (pintype "power_in"))
    )
    (net (code "52") (name "VUSB") (class "Default")
      (node (ref "W6C4") (pin "1") (pinfunction "1_1") (pintype "passive"))
      (node (ref "W6C9") (pin "1") (pinfunction "1_1") (pintype "passive"))
      (node (ref "W6F1") (pin "1") (pinfunction "1_1") (pintype "bidirectional"))
      (node (ref "W6J2") (pin "2") (pinfunction "2_2") (pintype "passive"))
      (node (ref "W6U1") (pin "7") (pinfunction "VBUS_7") (pintype "input"))
    )
    (net (code "53") (name "XTAL1") (class "Default")
      (node (ref "W6C8") (pin "1") (pinfunction "1_1") (pintype "passive"))
      (node (ref "W6Q1") (pin "P$3") (pinfunction "3_P$3") (pintype "passive"))
      (node (ref "W6R11") (pin "2") (pinfunction "2_2") (pintype "passive"))
      (node (ref "W6U1") (pin "17") (pinfunction "XTAL1_17") (pintype "bidirectional"))
    )
    (net (code "54") (name "XTAL2") (class "Default")
      (node (ref "W6C7") (pin "1") (pinfunction "1_1") (pintype "passive"))
      (node (ref "W6Q1") (pin "P$1") (pinfunction "1_P$1") (pintype "passive"))
      (node (ref "W6R11") (pin "1") (pinfunction "1_1") (pintype "passive"))
      (node (ref "W6U1") (pin "16") (pinfunction "XTAL2_16") (pintype "bidirectional"))
    )
    (net (code "55") (name "XUSB") (class "Default")
      (node (ref "W6F1") (pin "2") (pinfunction "2_2") (pintype "bidirectional"))
      (node (ref "W6X1") (pin "VBUS") (pinfunction "VBUS_VBUS") (pintype "bidirectional"))
    )
    (net (code "56") (name "unconnected-(W6SW1-Pad3)") (class "Default")
      (node (ref "W6SW1") (pin "3") (pinfunction "3_3") (pintype "bidirectional"))
    )
    (net (code "57") (name "unconnected-(W6SW2-Pad3)") (class "Default")
      (node (ref "W6SW2") (pin "3") (pinfunction "3_3") (pintype "bidirectional"))
    )
  )
)
